# V_SYS_Regulator.net
KiCad netlist of a schematic drawn in Altium Designer
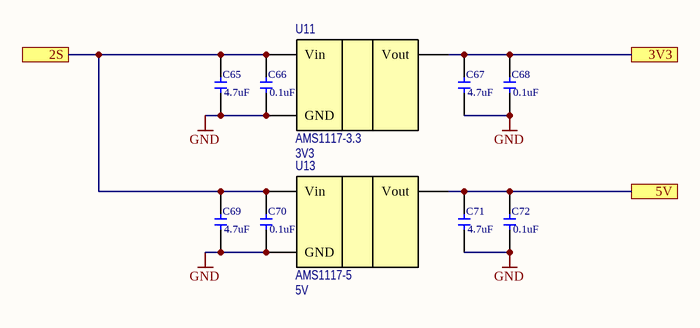
[diagram p0: V_SYS_Regulator.SchDoc]

(export (version "E")
  (design (tool "Eeschema 10.0.6"))
  (components
    (comp (ref "C65")
      (value "4.7uF")
      (footprint "CERCAP 0603")
      (description "Capacitor")
      (fields (field (name "VOLTAGE") "16V") (field (name "Comment") "CERCAP 0603 4.7uF 16V X7R"))
      (libsource (lib "!main") (part "!Capacitor"))
    )
    (comp (ref "C66")
      (value "0.1uF")
      (footprint "CERCAP 0402")
      (description "Capacitor")
      (fields (field (name "VOLTAGE") "50V") (field (name "Comment") "CERCAP 0402 0.1uF 50V X7R"))
      (libsource (lib "!main") (part "!Capacitor"))
    )
    (comp (ref "C67")
      (value "4.7uF")
      (footprint "CERCAP 0603")
      (description "Capacitor")
      (fields (field (name "VOLTAGE") "16V") (field (name "Comment") "CERCAP 0603 4.7uF 16V X7R"))
      (libsource (lib "!main") (part "!Capacitor"))
    )
    (comp (ref "C68")
      (value "0.1uF")
      (footprint "CERCAP 0402")
      (description "Capacitor")
      (fields (field (name "VOLTAGE") "50V") (field (name "Comment") "CERCAP 0402 0.1uF 50V X7R"))
      (libsource (lib "!main") (part "!Capacitor"))
    )
    (comp (ref "C69")
      (value "4.7uF")
      (footprint "CERCAP 0603")
      (description "Capacitor")
      (fields (field (name "VOLTAGE") "16V") (field (name "Comment") "CERCAP 0603 4.7uF 16V X7R"))
      (libsource (lib "!main") (part "!Capacitor"))
    )
    (comp (ref "C70")
      (value "0.1uF")
      (footprint "CERCAP 0402")
      (description "Capacitor")
      (fields (field (name "VOLTAGE") "50V") (field (name "Comment") "CERCAP 0402 0.1uF 50V X7R"))
      (libsource (lib "!main") (part "!Capacitor"))
    )
    (comp (ref "C71")
      (value "4.7uF")
      (footprint "CERCAP 0603")
      (description "Capacitor")
      (fields (field (name "VOLTAGE") "16V") (field (name "Comment") "CERCAP 0603 4.7uF 16V X7R"))
      (libsource (lib "!main") (part "!Capacitor"))
    )
    (comp (ref "C72")
      (value "0.1uF")
      (footprint "CERCAP 0402")
      (description "Capacitor")
      (fields (field (name "VOLTAGE") "50V") (field (name "Comment") "CERCAP 0402 0.1uF 50V X7R"))
      (libsource (lib "!main") (part "!Capacitor"))
    )
    (comp (ref "U11")
      (value "AMS1117-3.3")
      (footprint "SOT223")
      (description "generic ldo")
      (fields (field (name "ALTIUM_VALUE") "3V3"))
      (libsource (lib "power") (part "!Generic LDO"))
    )
    (comp (ref "U13")
      (value "AMS1117-5")
      (footprint "SOT223")
      (description "generic ldo")
      (fields (field (name "ALTIUM_VALUE") "5V"))
      (libsource (lib "power") (part "!Generic LDO"))
    )
  )
  (nets
    (net (code "1") (name "/2S") (class "Default")
      (node (ref "C65") (pin "2") (pintype "passive"))
      (node (ref "C66") (pin "2") (pintype "passive"))
      (node (ref "C69") (pin "2") (pintype "passive"))
      (node (ref "C70") (pin "2") (pintype "passive"))
      (node (ref "U11") (pin "Vin") (pinfunction "Vin_Vin") (pintype "passive"))
      (node (ref "U13") (pin "Vin") (pinfunction "Vin_Vin") (pintype "passive"))
    )
    (net (code "2") (name "/3V3") (class "Default")
      (node (ref "C67") (pin "2") (pintype "passive"))
      (node (ref "C68") (pin "2") (pintype "passive"))
      (node (ref "U11") (pin "Vout") (pinfunction "Vout_Vout") (pintype "passive"))
    )
    (net (code "3") (name "/5V") (class "Default")
      (node (ref "C71") (pin "2") (pintype "passive"))
      (node (ref "C72") (pin "2") (pintype "passive"))
      (node (ref "U13") (pin "Vout") (pinfunction "Vout_Vout") (pintype "passive"))
    )
    (net (code "4") (name "GND") (class "Default")
      (node (ref "C65") (pin "1") (pintype "passive"))
      (node (ref "C66") (pin "1") (pintype "passive"))
      (node (ref "C67") (pin "1") (pintype "passive"))
      (node (ref "C68") (pin "1") (pintype "passive"))
      (node (ref "C69") (pin "1") (pintype "passive"))
      (node (ref "C70") (pin "1") (pintype "passive"))
      (node (ref "C71") (pin "1") (pintype "passive"))
      (node (ref "C72") (pin "1") (pintype "passive"))
      (node (ref "U11") (pin "ADJ/GND") (pinfunction "GND_ADJ/GND") (pintype "passive"))
      (node (ref "U13") (pin "ADJ/GND") (pinfunction "GND_ADJ/GND") (pintype "passive"))
    )
  )
)
